# Interface.net
KiCad netlist of a schematic drawn in EAGLE
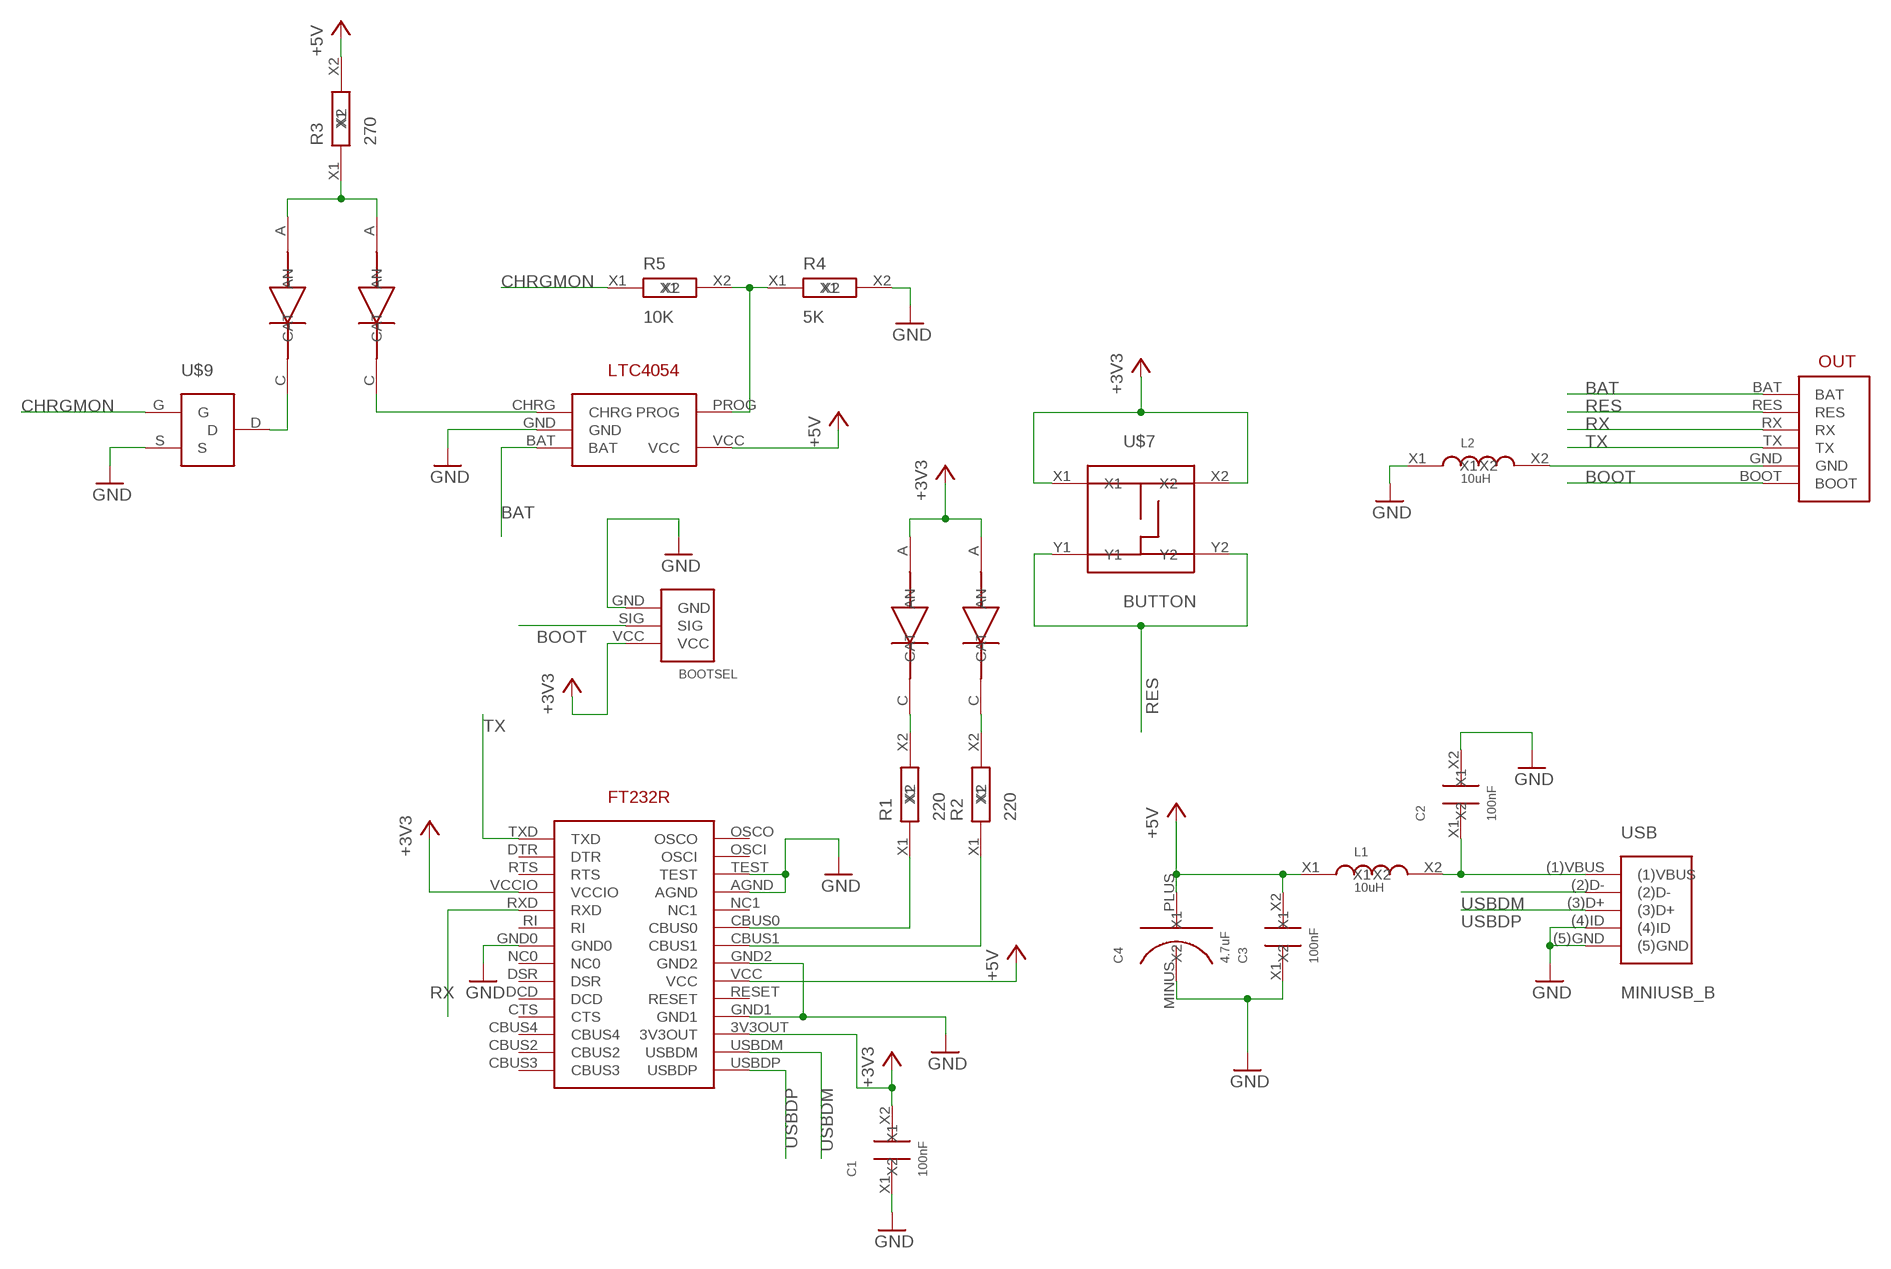
[diagram p0: schematic, sheet 1]

(export (version "E")
  (design (tool "Eeschema 10.0.6"))
  (components
    (comp (ref "BOOTSEL")
      (value "BOOT3PIN")
      (footprint "eagle-import:BOOT3PIN")
      (libsource (lib "eagle-import") (part "BOOT3PIN"))
    )
    (comp (ref "C1")
      (value "100nF")
      (footprint "eagle-import:SMD_2.1X1.25")
      (libsource (lib "eagle-import") (part "C_SMD_2.1X1.25"))
    )
    (comp (ref "C2")
      (value "100nF")
      (footprint "eagle-import:SMD_2.1X1.25")
      (libsource (lib "eagle-import") (part "C_SMD_2.1X1.25"))
    )
    (comp (ref "C3")
      (value "100nF")
      (footprint "eagle-import:SMD_2.1X1.25")
      (libsource (lib "eagle-import") (part "C_SMD_2.1X1.25"))
    )
    (comp (ref "C4")
      (value "4.7uF")
      (footprint "eagle-import:C_SMD_TA_A")
      (libsource (lib "eagle-import") (part "C_SMD_TA_A"))
    )
    (comp (ref "L1")
      (value "10uH")
      (footprint "eagle-import:SMD_2.1X1.25")
      (libsource (lib "eagle-import") (part "L_SMD_2.1X1.25"))
    )
    (comp (ref "L2")
      (value "10uH")
      (footprint "eagle-import:SMD_2.1X1.25")
      (libsource (lib "eagle-import") (part "L_SMD_2.1X1.25"))
    )
    (comp (ref "R1")
      (value "220")
      (footprint "eagle-import:SMD_2.1X1.25")
      (libsource (lib "eagle-import") (part "R_SMD_2.1X1.25"))
    )
    (comp (ref "R2")
      (value "220")
      (footprint "eagle-import:SMD_2.1X1.25")
      (libsource (lib "eagle-import") (part "R_SMD_2.1X1.25"))
    )
    (comp (ref "R3")
      (value "270")
      (footprint "eagle-import:SMD_2.1X1.25")
      (libsource (lib "eagle-import") (part "R_SMD_2.1X1.25"))
    )
    (comp (ref "R4")
      (value "5K")
      (footprint "eagle-import:SMD_2.1X1.25")
      (libsource (lib "eagle-import") (part "R_SMD_2.1X1.25"))
    )
    (comp (ref "R5")
      (value "10K")
      (footprint "eagle-import:SMD_2.1X1.25")
      (libsource (lib "eagle-import") (part "R_SMD_2.1X1.25"))
    )
    (comp (ref "U$1")
      (value "FT232R")
      (footprint "eagle-import:FT232")
      (libsource (lib "eagle-import") (part "FT232R"))
    )
    (comp (ref "U$2")
      (value "LTC4054")
      (footprint "eagle-import:LTC4054")
      (libsource (lib "eagle-import") (part "LTC4054"))
    )
    (comp (ref "U$3")
      (value "LED0805")
      (footprint "eagle-import:LED0805")
      (libsource (lib "eagle-import") (part "LED0805"))
    )
    (comp (ref "U$4")
      (value "LED0805")
      (footprint "eagle-import:LED0805")
      (libsource (lib "eagle-import") (part "LED0805"))
    )
    (comp (ref "U$5")
      (value "LED0805")
      (footprint "eagle-import:LED0805")
      (libsource (lib "eagle-import") (part "LED0805"))
    )
    (comp (ref "U$6")
      (value "LED0805")
      (footprint "eagle-import:LED0805")
      (libsource (lib "eagle-import") (part "LED0805"))
    )
    (comp (ref "U$7")
      (value "BUTTON")
      (footprint "eagle-import:BUTTON")
      (libsource (lib "eagle-import") (part "BUTTON"))
    )
    (comp (ref "U$8")
      (value "PLUG6PIN")
      (footprint "eagle-import:PLUG6PIN")
      (libsource (lib "eagle-import") (part "PLUG6PIN"))
    )
    (comp (ref "U$9")
      (value "IRFML8244TRPBF")
      (footprint "eagle-import:IRFML8244TRPBF")
      (libsource (lib "eagle-import") (part "IRFML8244TRPBF"))
    )
    (comp (ref "USB")
      (value "MINIUSB_B")
      (footprint "eagle-import:MINIUSB_B")
      (libsource (lib "eagle-import") (part "MINIUSB_B"))
    )
  )
  (nets
    (net (code "1") (name "+3V3") (class "Default")
      (node (ref "BOOTSEL") (pin "VCC") (pinfunction "VCC_VCC") (pintype "bidirectional"))
      (node (ref "C1") (pin "X2") (pinfunction "X2_X2") (pintype "bidirectional"))
      (node (ref "U$1") (pin "3V3OUT") (pinfunction "3V3OUT_3V3OUT") (pintype "bidirectional"))
      (node (ref "U$1") (pin "VCCIO") (pinfunction "VCCIO_VCCIO") (pintype "bidirectional"))
      (node (ref "U$4") (pin "A") (pinfunction "AN_A") (pintype "bidirectional"))
      (node (ref "U$6") (pin "A") (pinfunction "AN_A") (pintype "bidirectional"))
      (node (ref "U$7") (pin "X1") (pinfunction "X1_X1") (pintype "bidirectional"))
      (node (ref "U$7") (pin "X2") (pinfunction "X2_X2") (pintype "bidirectional"))
    )
    (net (code "2") (name "+5V") (class "Default")
      (node (ref "C3") (pin "X2") (pinfunction "X2_X2") (pintype "bidirectional"))
      (node (ref "C4") (pin "PLUS") (pinfunction "X2_PLUS") (pintype "bidirectional"))
      (node (ref "L1") (pin "X1") (pinfunction "X1_X1") (pintype "bidirectional"))
      (node (ref "R3") (pin "X2") (pinfunction "X2_X2") (pintype "bidirectional"))
      (node (ref "U$1") (pin "VCC") (pinfunction "VCC_VCC") (pintype "bidirectional"))
      (node (ref "U$2") (pin "VCC") (pinfunction "VCC_VCC") (pintype "bidirectional"))
    )
    (net (code "3") (name "/BAT") (class "Default")
      (node (ref "U$2") (pin "BAT") (pinfunction "BAT_BAT") (pintype "bidirectional"))
      (node (ref "U$8") (pin "BAT") (pinfunction "BAT_BAT") (pintype "bidirectional"))
    )
    (net (code "4") (name "/BOOT") (class "Default")
      (node (ref "BOOTSEL") (pin "SIG") (pinfunction "SIG_SIG") (pintype "bidirectional"))
      (node (ref "U$8") (pin "BOOT") (pinfunction "BOOT_BOOT") (pintype "bidirectional"))
    )
    (net (code "5") (name "/CHRGMON") (class "Default")
      (node (ref "R5") (pin "X1") (pinfunction "X1_X1") (pintype "bidirectional"))
      (node (ref "U$9") (pin "G") (pinfunction "G_G") (pintype "bidirectional"))
    )
    (net (code "6") (name "/RES") (class "Default")
      (node (ref "U$7") (pin "Y1") (pinfunction "Y1_Y1") (pintype "bidirectional"))
      (node (ref "U$7") (pin "Y2") (pinfunction "Y2_Y2") (pintype "bidirectional"))
      (node (ref "U$8") (pin "RES") (pinfunction "RES_RES") (pintype "bidirectional"))
    )
    (net (code "7") (name "/RX") (class "Default")
      (node (ref "U$1") (pin "RXD") (pinfunction "RXD_RXD") (pintype "bidirectional"))
      (node (ref "U$8") (pin "RX") (pinfunction "RX_RX") (pintype "bidirectional"))
    )
    (net (code "8") (name "/TX") (class "Default")
      (node (ref "U$1") (pin "TXD") (pinfunction "TXD_TXD") (pintype "bidirectional"))
      (node (ref "U$8") (pin "TX") (pinfunction "TX_TX") (pintype "bidirectional"))
    )
    (net (code "9") (name "/USBDM") (class "Default")
      (node (ref "U$1") (pin "USBDM") (pinfunction "USBDM_USBDM") (pintype "bidirectional"))
      (node (ref "USB") (pin "(2)D-") (pinfunction "(2)D-_(2)D-") (pintype "bidirectional"))
    )
    (net (code "10") (name "/USBDP") (class "Default")
      (node (ref "U$1") (pin "USBDP") (pinfunction "USBDP_USBDP") (pintype "bidirectional"))
      (node (ref "USB") (pin "(3)D+") (pinfunction "(3)D+_(3)D+") (pintype "bidirectional"))
    )
    (net (code "11") (name "GND") (class "Default")
      (node (ref "BOOTSEL") (pin "GND") (pinfunction "GND_GND") (pintype "bidirectional"))
      (node (ref "C1") (pin "X1") (pinfunction "X1_X1") (pintype "bidirectional"))
      (node (ref "C2") (pin "X2") (pinfunction "X2_X2") (pintype "bidirectional"))
      (node (ref "C3") (pin "X1") (pinfunction "X1_X1") (pintype "bidirectional"))
      (node (ref "C4") (pin "MINUS") (pinfunction "X1_MINUS") (pintype "bidirectional"))
      (node (ref "L2") (pin "X1") (pinfunction "X1_X1") (pintype "bidirectional"))
      (node (ref "R4") (pin "X2") (pinfunction "X2_X2") (pintype "bidirectional"))
      (node (ref "U$1") (pin "AGND") (pinfunction "AGND_AGND") (pintype "bidirectional"))
      (node (ref "U$1") (pin "GND0") (pinfunction "GND0_GND0") (pintype "bidirectional"))
      (node (ref "U$1") (pin "GND1") (pinfunction "GND1_GND1") (pintype "bidirectional"))
      (node (ref "U$1") (pin "GND2") (pinfunction "GND2_GND2") (pintype "bidirectional"))
      (node (ref "U$1") (pin "TEST") (pinfunction "TEST_TEST") (pintype "bidirectional"))
      (node (ref "U$2") (pin "GND") (pinfunction "GND_GND") (pintype "bidirectional"))
      (node (ref "U$9") (pin "S") (pinfunction "S_S") (pintype "bidirectional"))
      (node (ref "USB") (pin "(4)ID") (pinfunction "(4)ID_(4)ID") (pintype "bidirectional"))
      (node (ref "USB") (pin "(5)GND") (pinfunction "(5)GND_(5)GND") (pintype "bidirectional"))
    )
    (net (code "12") (name "Net-(C2-PadX1)") (class "Default")
      (node (ref "C2") (pin "X1") (pinfunction "X1_X1") (pintype "bidirectional"))
      (node (ref "L1") (pin "X2") (pinfunction "X2_X2") (pintype "bidirectional"))
      (node (ref "USB") (pin "(1)VBUS") (pinfunction "(1)VBUS_(1)VBUS") (pintype "bidirectional"))
    )
    (net (code "13") (name "Net-(L2-PadX2)") (class "Default")
      (node (ref "L2") (pin "X2") (pinfunction "X2_X2") (pintype "bidirectional"))
      (node (ref "U$8") (pin "GND") (pinfunction "GND_GND") (pintype "bidirectional"))
    )
    (net (code "14") (name "Net-(R1-PadX1)") (class "Default")
      (node (ref "R1") (pin "X1") (pinfunction "X1_X1") (pintype "bidirectional"))
      (node (ref "U$1") (pin "CBUS0") (pinfunction "CBUS0_CBUS0") (pintype "bidirectional"))
    )
    (net (code "15") (name "Net-(R2-PadX1)") (class "Default")
      (node (ref "R2") (pin "X1") (pinfunction "X1_X1") (pintype "bidirectional"))
      (node (ref "U$1") (pin "CBUS1") (pinfunction "CBUS1_CBUS1") (pintype "bidirectional"))
    )
    (net (code "16") (name "Net-(R4-PadX1)") (class "Default")
      (node (ref "R4") (pin "X1") (pinfunction "X1_X1") (pintype "bidirectional"))
      (node (ref "R5") (pin "X2") (pinfunction "X2_X2") (pintype "bidirectional"))
      (node (ref "U$2") (pin "PROG") (pinfunction "PROG_PROG") (pintype "bidirectional"))
    )
    (net (code "17") (name "Net-(U$3-AN)") (class "Default")
      (node (ref "R3") (pin "X1") (pinfunction "X1_X1") (pintype "bidirectional"))
      (node (ref "U$3") (pin "A") (pinfunction "AN_A") (pintype "bidirectional"))
      (node (ref "U$5") (pin "A") (pinfunction "AN_A") (pintype "bidirectional"))
    )
    (net (code "18") (name "Net-(U$3-CAT)") (class "Default")
      (node (ref "U$2") (pin "CHRG") (pinfunction "CHRG_CHRG") (pintype "bidirectional"))
      (node (ref "U$3") (pin "C") (pinfunction "CAT_C") (pintype "bidirectional"))
    )
    (net (code "19") (name "Net-(U$4-CAT)") (class "Default")
      (node (ref "R1") (pin "X2") (pinfunction "X2_X2") (pintype "bidirectional"))
      (node (ref "U$4") (pin "C") (pinfunction "CAT_C") (pintype "bidirectional"))
    )
    (net (code "20") (name "Net-(U$5-CAT)") (class "Default")
      (node (ref "U$5") (pin "C") (pinfunction "CAT_C") (pintype "bidirectional"))
      (node (ref "U$9") (pin "D") (pinfunction "D_D") (pintype "bidirectional"))
    )
    (net (code "21") (name "Net-(U$6-CAT)") (class "Default")
      (node (ref "R2") (pin "X2") (pinfunction "X2_X2") (pintype "bidirectional"))
      (node (ref "U$6") (pin "C") (pinfunction "CAT_C") (pintype "bidirectional"))
    )
    (net (code "22") (name "unconnected-(U$1-PadCBUS2)") (class "Default")
      (node (ref "U$1") (pin "CBUS2") (pinfunction "CBUS2_CBUS2") (pintype "bidirectional"))
    )
    (net (code "23") (name "unconnected-(U$1-PadCBUS3)") (class "Default")
      (node (ref "U$1") (pin "CBUS3") (pinfunction "CBUS3_CBUS3") (pintype "bidirectional"))
    )
    (net (code "24") (name "unconnected-(U$1-PadCBUS4)") (class "Default")
      (node (ref "U$1") (pin "CBUS4") (pinfunction "CBUS4_CBUS4") (pintype "bidirectional"))
    )
    (net (code "25") (name "unconnected-(U$1-PadCTS)") (class "Default")
      (node (ref "U$1") (pin "CTS") (pinfunction "CTS_CTS") (pintype "bidirectional"))
    )
    (net (code "26") (name "unconnected-(U$1-PadDCD)") (class "Default")
      (node (ref "U$1") (pin "DCD") (pinfunction "DCD_DCD") (pintype "bidirectional"))
    )
    (net (code "27") (name "unconnected-(U$1-PadDSR)") (class "Default")
      (node (ref "U$1") (pin "DSR") (pinfunction "DSR_DSR") (pintype "bidirectional"))
    )
    (net (code "28") (name "unconnected-(U$1-PadDTR)") (class "Default")
      (node (ref "U$1") (pin "DTR") (pinfunction "DTR_DTR") (pintype "bidirectional"))
    )
    (net (code "29") (name "unconnected-(U$1-PadNC0)") (class "Default")
      (node (ref "U$1") (pin "NC0") (pinfunction "NC0_NC0") (pintype "bidirectional"))
    )
    (net (code "30") (name "unconnected-(U$1-PadNC1)") (class "Default")
      (node (ref "U$1") (pin "NC1") (pinfunction "NC1_NC1") (pintype "bidirectional"))
    )
    (net (code "31") (name "unconnected-(U$1-PadOSCI)") (class "Default")
      (node (ref "U$1") (pin "OSCI") (pinfunction "OSCI_OSCI") (pintype "bidirectional"))
    )
    (net (code "32") (name "unconnected-(U$1-PadOSCO)") (class "Default")
      (node (ref "U$1") (pin "OSCO") (pinfunction "OSCO_OSCO") (pintype "bidirectional"))
    )
    (net (code "33") (name "unconnected-(U$1-PadRESET)") (class "Default")
      (node (ref "U$1") (pin "RESET") (pinfunction "RESET_RESET") (pintype "bidirectional"))
    )
    (net (code "34") (name "unconnected-(U$1-PadRI)") (class "Default")
      (node (ref "U$1") (pin "RI") (pinfunction "RI_RI") (pintype "bidirectional"))
    )
    (net (code "35") (name "unconnected-(U$1-PadRTS)") (class "Default")
      (node (ref "U$1") (pin "RTS") (pinfunction "RTS_RTS") (pintype "bidirectional"))
    )
  )
)
